# RS485.net
KiCad netlist of a schematic drawn in Altium Designer
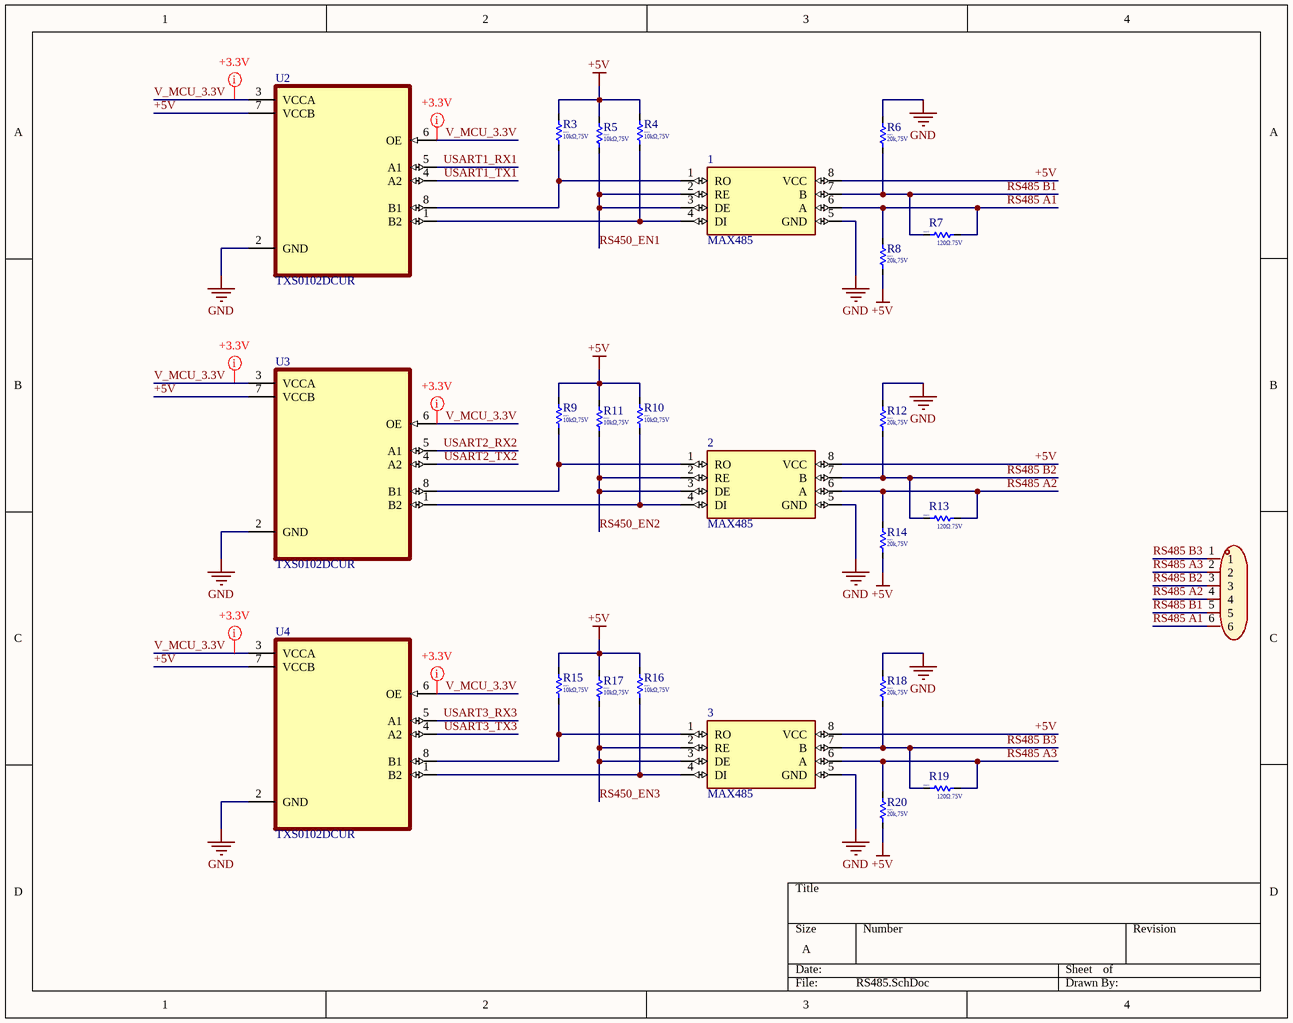
[diagram p0: RS485.SchDoc]

(export (version "E")
  (design (tool "Eeschema 10.0.6"))
  (components
    (comp (ref "1")
      (value "MAX485")
      (footprint "MAX485")
      (description "1/1 Transceiver Half RS422, RS485 8-SOIC")
      (fields (field (name "MANUFACTURER") "Maxim Integrated"))
      (libsource (lib "IC") (part "MAX485"))
    )
    (comp (ref "2")
      (value "MAX485")
      (footprint "MAX485")
      (description "1/1 Transceiver Half RS422, RS485 8-SOIC")
      (fields (field (name "MANUFACTURER") "Maxim Integrated"))
      (libsource (lib "IC") (part "MAX485"))
    )
    (comp (ref "3")
      (value "MAX485")
      (footprint "MAX485")
      (description "1/1 Transceiver Half RS422, RS485 8-SOIC")
      (fields (field (name "MANUFACTURER") "Maxim Integrated"))
      (libsource (lib "IC") (part "MAX485"))
    )
    (comp (ref "CN1")
      (value "DB128V-5.08-6P-GN-S")
      (footprint "6P_P=5.08mm")
      (description "1x6P 20A -40℃~+105℃ 300V Green 12~30 Direct Insert 5.08mm 2.5 1 6 Plugin,P=5.08mm Screw Terminal")
      (fields (field (name "MANUFACTURER") "DORABO"))
      (libsource (lib "connector_button") (part "DB128V-5.08-6P-GN-S"))
    )
    (comp (ref "R3")
      (value "10kΩ,75V")
      (footprint "R0603")
      (description "100mW Thick Film Resistors ±1% ±400ppm/℃ 10Ω 0603 Chip Resistor - Surface Mount ROHS")
      (fields
        (field (name "MANUFACTURER") "UNI-ROYAL(Uniroyal Elec)")
        (field (name "MPN") "0603WAF1002T5E")
        (field (name "PACKAGE") "0603")
      )
      (libsource (lib "RCL") (part "0603WAF100JT5E"))
    )
    (comp (ref "R4")
      (value "10kΩ,75V")
      (footprint "R0603")
      (description "100mW Thick Film Resistors ±1% ±400ppm/℃ 10Ω 0603 Chip Resistor - Surface Mount ROHS")
      (fields
        (field (name "MANUFACTURER") "UNI-ROYAL(Uniroyal Elec)")
        (field (name "MPN") "0603WAF1002T5E")
        (field (name "PACKAGE") "0603")
      )
      (libsource (lib "RCL") (part "0603WAF100JT5E"))
    )
    (comp (ref "R5")
      (value "10kΩ,75V")
      (footprint "R0603")
      (description "100mW Thick Film Resistors ±1% ±400ppm/℃ 10Ω 0603 Chip Resistor - Surface Mount ROHS")
      (fields
        (field (name "MANUFACTURER") "UNI-ROYAL(Uniroyal Elec)")
        (field (name "MPN") "0603WAF1002T5E")
        (field (name "PACKAGE") "0603")
      )
      (libsource (lib "RCL") (part "0603WAF100JT5E"))
    )
    (comp (ref "R6")
      (value "20k,75V")
      (footprint "R0603")
      (description "100mW Thick Film Resistors ±100ppm/℃ ±1% 20kΩ 0603 Chip Resistor - Surface Mount ROHS")
      (fields
        (field (name "MANUFACTURER") "UNI-ROYAL(Uniroyal Elec)")
        (field (name "MPN") "0603WAF1002T5E")
        (field (name "PACKAGE") "0603")
      )
      (libsource (lib "RCL") (part "0603WAF2002T5E"))
    )
    (comp (ref "R7")
      (value "120Ω.75V")
      (footprint "R0603")
      (description "100mW Thick Film Resistors 75V ±100ppm/℃ ±1% 120Ω 0603 Chip Resistor - Surface Mount ROHS")
      (fields
        (field (name "MANUFACTURER") "UNI-ROYAL(Uniroyal Elec)")
        (field (name "MPN") "0603WAF1002T5E")
        (field (name "PACKAGE") "0603")
      )
      (libsource (lib "RCL") (part "0603WAF1200T5E"))
    )
    (comp (ref "R8")
      (value "20k,75V")
      (footprint "R0603")
      (description "100mW Thick Film Resistors ±100ppm/℃ ±1% 20kΩ 0603 Chip Resistor - Surface Mount ROHS")
      (fields
        (field (name "MANUFACTURER") "UNI-ROYAL(Uniroyal Elec)")
        (field (name "MPN") "0603WAF1002T5E")
        (field (name "PACKAGE") "0603")
      )
      (libsource (lib "RCL") (part "0603WAF2002T5E"))
    )
    (comp (ref "R9")
      (value "10kΩ,75V")
      (footprint "R0603")
      (description "100mW Thick Film Resistors ±1% ±400ppm/℃ 10Ω 0603 Chip Resistor - Surface Mount ROHS")
      (fields
        (field (name "MANUFACTURER") "UNI-ROYAL(Uniroyal Elec)")
        (field (name "MPN") "0603WAF1002T5E")
        (field (name "PACKAGE") "0603")
      )
      (libsource (lib "RCL") (part "0603WAF100JT5E"))
    )
    (comp (ref "R10")
      (value "10kΩ,75V")
      (footprint "R0603")
      (description "100mW Thick Film Resistors ±1% ±400ppm/℃ 10Ω 0603 Chip Resistor - Surface Mount ROHS")
      (fields
        (field (name "MANUFACTURER") "UNI-ROYAL(Uniroyal Elec)")
        (field (name "MPN") "0603WAF1002T5E")
        (field (name "PACKAGE") "0603")
      )
      (libsource (lib "RCL") (part "0603WAF100JT5E"))
    )
    (comp (ref "R11")
      (value "10kΩ,75V")
      (footprint "R0603")
      (description "100mW Thick Film Resistors ±1% ±400ppm/℃ 10Ω 0603 Chip Resistor - Surface Mount ROHS")
      (fields
        (field (name "MANUFACTURER") "UNI-ROYAL(Uniroyal Elec)")
        (field (name "MPN") "0603WAF1002T5E")
        (field (name "PACKAGE") "0603")
      )
      (libsource (lib "RCL") (part "0603WAF100JT5E"))
    )
    (comp (ref "R12")
      (value "20k,75V")
      (footprint "R0603")
      (description "100mW Thick Film Resistors ±100ppm/℃ ±1% 20kΩ 0603 Chip Resistor - Surface Mount ROHS")
      (fields
        (field (name "MANUFACTURER") "UNI-ROYAL(Uniroyal Elec)")
        (field (name "MPN") "0603WAF1002T5E")
        (field (name "PACKAGE") "0603")
      )
      (libsource (lib "RCL") (part "0603WAF2002T5E"))
    )
    (comp (ref "R13")
      (value "120Ω.75V")
      (footprint "R0603")
      (description "100mW Thick Film Resistors 75V ±100ppm/℃ ±1% 120Ω 0603 Chip Resistor - Surface Mount ROHS")
      (fields
        (field (name "MANUFACTURER") "UNI-ROYAL(Uniroyal Elec)")
        (field (name "MPN") "0603WAF1002T5E")
        (field (name "PACKAGE") "0603")
      )
      (libsource (lib "RCL") (part "0603WAF1200T5E"))
    )
    (comp (ref "R14")
      (value "20k,75V")
      (footprint "R0603")
      (description "100mW Thick Film Resistors ±100ppm/℃ ±1% 20kΩ 0603 Chip Resistor - Surface Mount ROHS")
      (fields
        (field (name "MANUFACTURER") "UNI-ROYAL(Uniroyal Elec)")
        (field (name "MPN") "0603WAF1002T5E")
        (field (name "PACKAGE") "0603")
      )
      (libsource (lib "RCL") (part "0603WAF2002T5E"))
    )
    (comp (ref "R15")
      (value "10kΩ,75V")
      (footprint "R0603")
      (description "100mW Thick Film Resistors ±1% ±400ppm/℃ 10Ω 0603 Chip Resistor - Surface Mount ROHS")
      (fields
        (field (name "MANUFACTURER") "UNI-ROYAL(Uniroyal Elec)")
        (field (name "MPN") "0603WAF1002T5E")
        (field (name "PACKAGE") "0603")
      )
      (libsource (lib "RCL") (part "0603WAF100JT5E"))
    )
    (comp (ref "R16")
      (value "10kΩ,75V")
      (footprint "R0603")
      (description "100mW Thick Film Resistors ±1% ±400ppm/℃ 10Ω 0603 Chip Resistor - Surface Mount ROHS")
      (fields
        (field (name "MANUFACTURER") "UNI-ROYAL(Uniroyal Elec)")
        (field (name "MPN") "0603WAF1002T5E")
        (field (name "PACKAGE") "0603")
      )
      (libsource (lib "RCL") (part "0603WAF100JT5E"))
    )
    (comp (ref "R17")
      (value "10kΩ,75V")
      (footprint "R0603")
      (description "100mW Thick Film Resistors ±1% ±400ppm/℃ 10Ω 0603 Chip Resistor - Surface Mount ROHS")
      (fields
        (field (name "MANUFACTURER") "UNI-ROYAL(Uniroyal Elec)")
        (field (name "MPN") "0603WAF1002T5E")
        (field (name "PACKAGE") "0603")
      )
      (libsource (lib "RCL") (part "0603WAF100JT5E"))
    )
    (comp (ref "R18")
      (value "20k,75V")
      (footprint "R0603")
      (description "100mW Thick Film Resistors ±100ppm/℃ ±1% 20kΩ 0603 Chip Resistor - Surface Mount ROHS")
      (fields
        (field (name "MANUFACTURER") "UNI-ROYAL(Uniroyal Elec)")
        (field (name "MPN") "0603WAF1002T5E")
        (field (name "PACKAGE") "0603")
      )
      (libsource (lib "RCL") (part "0603WAF2002T5E"))
    )
    (comp (ref "R19")
      (value "120Ω.75V")
      (footprint "R0603")
      (description "100mW Thick Film Resistors 75V ±100ppm/℃ ±1% 120Ω 0603 Chip Resistor - Surface Mount ROHS")
      (fields
        (field (name "MANUFACTURER") "UNI-ROYAL(Uniroyal Elec)")
        (field (name "MPN") "0603WAF1002T5E")
        (field (name "PACKAGE") "0603")
      )
      (libsource (lib "RCL") (part "0603WAF1200T5E"))
    )
    (comp (ref "R20")
      (value "20k,75V")
      (footprint "R0603")
      (description "100mW Thick Film Resistors ±100ppm/℃ ±1% 20kΩ 0603 Chip Resistor - Surface Mount ROHS")
      (fields
        (field (name "MANUFACTURER") "UNI-ROYAL(Uniroyal Elec)")
        (field (name "MPN") "0603WAF1002T5E")
        (field (name "PACKAGE") "0603")
      )
      (libsource (lib "RCL") (part "0603WAF2002T5E"))
    )
    (comp (ref "U2")
      (value "TXS0102DCUR")
      (footprint "IC:8-VSSOP")
      (fields (field (name "MANUFACTURER") "Texas Instruments"))
      (libsource (lib "IC") (part "TXS0102DCUR"))
    )
    (comp (ref "U3")
      (value "TXS0102DCUR")
      (footprint "IC:8-VSSOP")
      (fields (field (name "MANUFACTURER") "Texas Instruments"))
      (libsource (lib "IC") (part "TXS0102DCUR"))
    )
    (comp (ref "U4")
      (value "TXS0102DCUR")
      (footprint "IC:8-VSSOP")
      (fields (field (name "MANUFACTURER") "Texas Instruments"))
      (libsource (lib "IC") (part "TXS0102DCUR"))
    )
  )
  (nets
    (net (code "1") (name "+5V") (class "Default")
      (node (ref "1") (pin "8") (pinfunction "VCC_8") (pintype "bidirectional"))
      (node (ref "2") (pin "8") (pinfunction "VCC_8") (pintype "bidirectional"))
      (node (ref "3") (pin "8") (pinfunction "VCC_8") (pintype "bidirectional"))
      (node (ref "R10") (pin "2") (pinfunction "2_2") (pintype "passive"))
      (node (ref "R11") (pin "2") (pinfunction "2_2") (pintype "passive"))
      (node (ref "R14") (pin "1") (pinfunction "1_1") (pintype "passive"))
      (node (ref "R15") (pin "2") (pinfunction "2_2") (pintype "passive"))
      (node (ref "R16") (pin "2") (pinfunction "2_2") (pintype "passive"))
      (node (ref "R17") (pin "2") (pinfunction "2_2") (pintype "passive"))
      (node (ref "R20") (pin "1") (pinfunction "1_1") (pintype "passive"))
      (node (ref "R3") (pin "2") (pinfunction "2_2") (pintype "passive"))
      (node (ref "R4") (pin "2") (pinfunction "2_2") (pintype "passive"))
      (node (ref "R5") (pin "2") (pinfunction "2_2") (pintype "passive"))
      (node (ref "R8") (pin "1") (pinfunction "1_1") (pintype "passive"))
      (node (ref "R9") (pin "2") (pinfunction "2_2") (pintype "passive"))
      (node (ref "U2") (pin "7") (pinfunction "VCCB_7") (pintype "power_in"))
      (node (ref "U3") (pin "7") (pinfunction "VCCB_7") (pintype "power_in"))
      (node (ref "U4") (pin "7") (pinfunction "VCCB_7") (pintype "power_in"))
    )
    (net (code "2") (name "/RS450_EN1") (class "Default")
      (node (ref "1") (pin "2") (pinfunction "RE_2") (pintype "bidirectional"))
      (node (ref "1") (pin "3") (pinfunction "DE_3") (pintype "bidirectional"))
      (node (ref "R5") (pin "1") (pinfunction "1_1") (pintype "passive"))
    )
    (net (code "3") (name "/RS450_EN2") (class "Default")
      (node (ref "2") (pin "2") (pinfunction "RE_2") (pintype "bidirectional"))
      (node (ref "2") (pin "3") (pinfunction "DE_3") (pintype "bidirectional"))
      (node (ref "R11") (pin "1") (pinfunction "1_1") (pintype "passive"))
    )
    (net (code "4") (name "/RS450_EN3") (class "Default")
      (node (ref "3") (pin "2") (pinfunction "RE_2") (pintype "bidirectional"))
      (node (ref "3") (pin "3") (pinfunction "DE_3") (pintype "bidirectional"))
      (node (ref "R17") (pin "1") (pinfunction "1_1") (pintype "passive"))
    )
    (net (code "5") (name "/RS485 A1") (class "Default")
      (node (ref "1") (pin "6") (pinfunction "A_6") (pintype "bidirectional"))
      (node (ref "CN1") (pin "6") (pinfunction "6_6") (pintype "passive"))
      (node (ref "R7") (pin "2") (pinfunction "2_2") (pintype "passive"))
      (node (ref "R8") (pin "2") (pinfunction "2_2") (pintype "passive"))
    )
    (net (code "6") (name "/RS485 A2") (class "Default")
      (node (ref "2") (pin "6") (pinfunction "A_6") (pintype "bidirectional"))
      (node (ref "CN1") (pin "4") (pinfunction "4_4") (pintype "passive"))
      (node (ref "R13") (pin "2") (pinfunction "2_2") (pintype "passive"))
      (node (ref "R14") (pin "2") (pinfunction "2_2") (pintype "passive"))
    )
    (net (code "7") (name "/RS485 A3") (class "Default")
      (node (ref "3") (pin "6") (pinfunction "A_6") (pintype "bidirectional"))
      (node (ref "CN1") (pin "2") (pinfunction "2_2") (pintype "passive"))
      (node (ref "R19") (pin "2") (pinfunction "2_2") (pintype "passive"))
      (node (ref "R20") (pin "2") (pinfunction "2_2") (pintype "passive"))
    )
    (net (code "8") (name "/RS485 B1") (class "Default")
      (node (ref "1") (pin "7") (pinfunction "B_7") (pintype "bidirectional"))
      (node (ref "CN1") (pin "5") (pinfunction "5_5") (pintype "passive"))
      (node (ref "R6") (pin "1") (pinfunction "1_1") (pintype "passive"))
      (node (ref "R7") (pin "1") (pinfunction "1_1") (pintype "passive"))
    )
    (net (code "9") (name "/RS485 B2") (class "Default")
      (node (ref "2") (pin "7") (pinfunction "B_7") (pintype "bidirectional"))
      (node (ref "CN1") (pin "3") (pinfunction "3_3") (pintype "passive"))
      (node (ref "R12") (pin "1") (pinfunction "1_1") (pintype "passive"))
      (node (ref "R13") (pin "1") (pinfunction "1_1") (pintype "passive"))
    )
    (net (code "10") (name "/RS485 B3") (class "Default")
      (node (ref "3") (pin "7") (pinfunction "B_7") (pintype "bidirectional"))
      (node (ref "CN1") (pin "1") (pinfunction "1_1") (pintype "passive"))
      (node (ref "R18") (pin "1") (pinfunction "1_1") (pintype "passive"))
      (node (ref "R19") (pin "1") (pinfunction "1_1") (pintype "passive"))
    )
    (net (code "11") (name "/USART1_RX1") (class "Default")
      (node (ref "U2") (pin "5") (pinfunction "A1_5") (pintype "bidirectional"))
    )
    (net (code "12") (name "/USART1_TX1") (class "Default")
      (node (ref "U2") (pin "4") (pinfunction "A2_4") (pintype "bidirectional"))
    )
    (net (code "13") (name "/USART2_RX2") (class "Default")
      (node (ref "U3") (pin "5") (pinfunction "A1_5") (pintype "bidirectional"))
    )
    (net (code "14") (name "/USART2_TX2") (class "Default")
      (node (ref "U3") (pin "4") (pinfunction "A2_4") (pintype "bidirectional"))
    )
    (net (code "15") (name "/USART3_RX3") (class "Default")
      (node (ref "U4") (pin "5") (pinfunction "A1_5") (pintype "bidirectional"))
    )
    (net (code "16") (name "/USART3_TX3") (class "Default")
      (node (ref "U4") (pin "4") (pinfunction "A2_4") (pintype "bidirectional"))
    )
    (net (code "17") (name "/V_MCU_3.3V") (class "Default")
      (node (ref "U2") (pin "3") (pinfunction "VCCA_3") (pintype "power_in"))
      (node (ref "U2") (pin "6") (pinfunction "OE_6") (pintype "input"))
      (node (ref "U3") (pin "3") (pinfunction "VCCA_3") (pintype "power_in"))
      (node (ref "U3") (pin "6") (pinfunction "OE_6") (pintype "input"))
      (node (ref "U4") (pin "3") (pinfunction "VCCA_3") (pintype "power_in"))
      (node (ref "U4") (pin "6") (pinfunction "OE_6") (pintype "input"))
    )
    (net (code "18") (name "GND") (class "Default")
      (node (ref "1") (pin "5") (pinfunction "GND_5") (pintype "bidirectional"))
      (node (ref "2") (pin "5") (pinfunction "GND_5") (pintype "bidirectional"))
      (node (ref "3") (pin "5") (pinfunction "GND_5") (pintype "bidirectional"))
      (node (ref "R12") (pin "2") (pinfunction "2_2") (pintype "passive"))
      (node (ref "R18") (pin "2") (pinfunction "2_2") (pintype "passive"))
      (node (ref "R6") (pin "2") (pinfunction "2_2") (pintype "passive"))
      (node (ref "U2") (pin "2") (pinfunction "GND_2") (pintype "power_in"))
      (node (ref "U3") (pin "2") (pinfunction "GND_2") (pintype "power_in"))
      (node (ref "U4") (pin "2") (pinfunction "GND_2") (pintype "power_in"))
    )
    (net (code "19") (name "Net-(1-DI)") (class "Default")
      (node (ref "1") (pin "4") (pinfunction "DI_4") (pintype "bidirectional"))
      (node (ref "R4") (pin "1") (pinfunction "1_1") (pintype "passive"))
      (node (ref "U2") (pin "1") (pinfunction "B2_1") (pintype "bidirectional"))
    )
    (net (code "20") (name "Net-(1-RO)") (class "Default")
      (node (ref "1") (pin "1") (pinfunction "RO_1") (pintype "bidirectional"))
      (node (ref "R3") (pin "1") (pinfunction "1_1") (pintype "passive"))
      (node (ref "U2") (pin "8") (pinfunction "B1_8") (pintype "bidirectional"))
    )
    (net (code "21") (name "Net-(2-DI)") (class "Default")
      (node (ref "2") (pin "4") (pinfunction "DI_4") (pintype "bidirectional"))
      (node (ref "R10") (pin "1") (pinfunction "1_1") (pintype "passive"))
      (node (ref "U3") (pin "1") (pinfunction "B2_1") (pintype "bidirectional"))
    )
    (net (code "22") (name "Net-(2-RO)") (class "Default")
      (node (ref "2") (pin "1") (pinfunction "RO_1") (pintype "bidirectional"))
      (node (ref "R9") (pin "1") (pinfunction "1_1") (pintype "passive"))
      (node (ref "U3") (pin "8") (pinfunction "B1_8") (pintype "bidirectional"))
    )
    (net (code "23") (name "Net-(3-DI)") (class "Default")
      (node (ref "3") (pin "4") (pinfunction "DI_4") (pintype "bidirectional"))
      (node (ref "R16") (pin "1") (pinfunction "1_1") (pintype "passive"))
      (node (ref "U4") (pin "1") (pinfunction "B2_1") (pintype "bidirectional"))
    )
    (net (code "24") (name "Net-(3-RO)") (class "Default")
      (node (ref "3") (pin "1") (pinfunction "RO_1") (pintype "bidirectional"))
      (node (ref "R15") (pin "1") (pinfunction "1_1") (pintype "passive"))
      (node (ref "U4") (pin "8") (pinfunction "B1_8") (pintype "bidirectional"))
    )
  )
)
